# STM32.net
KiCad netlist of a schematic drawn in Altium Designer
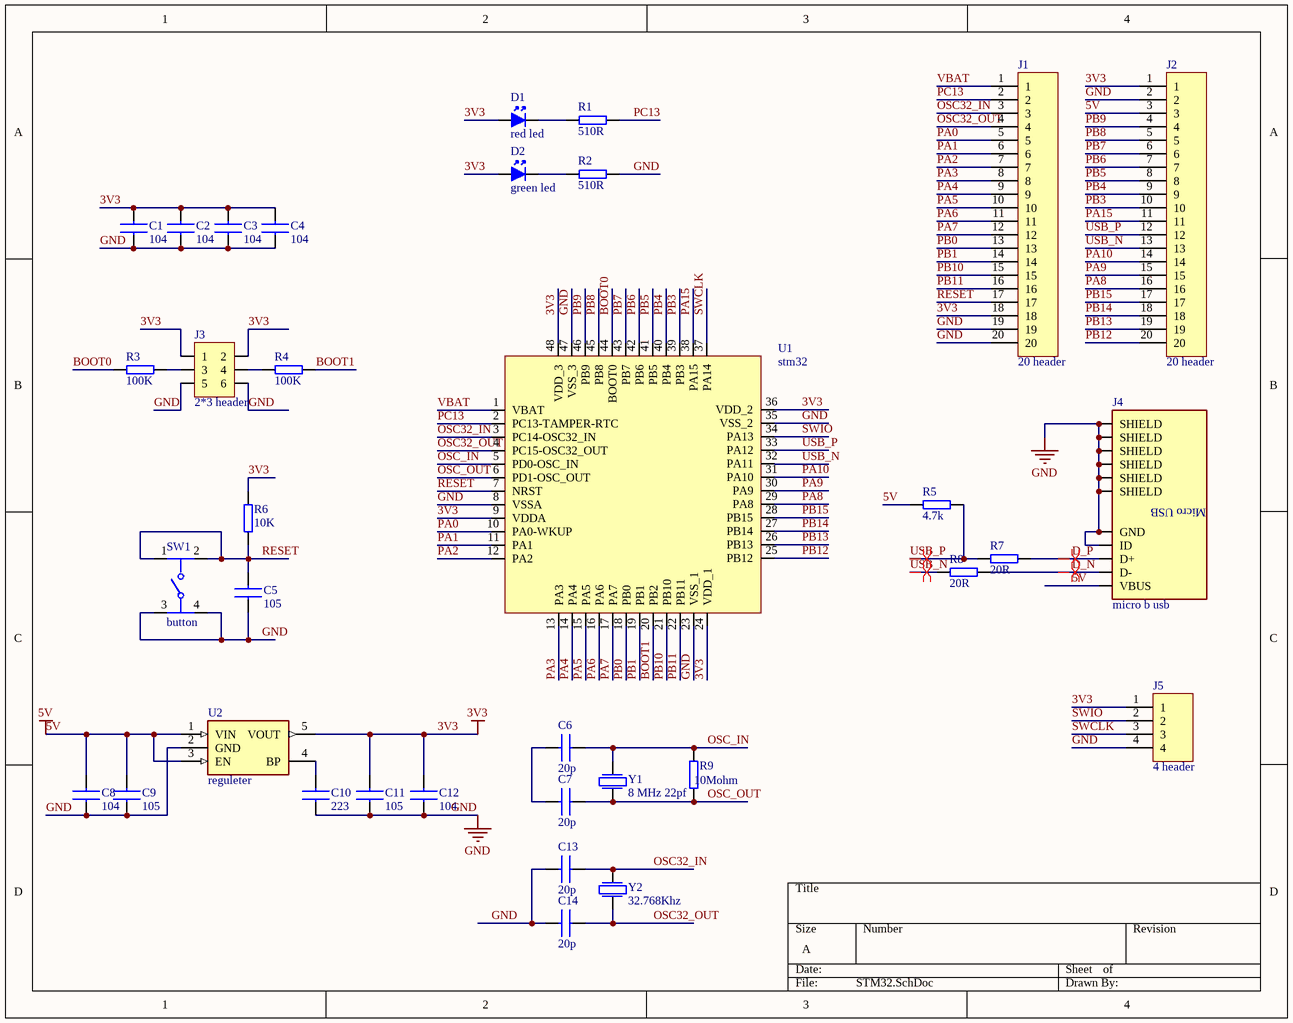
[diagram p0: STM32.SchDoc]

(export (version "E")
  (design (tool "Eeschema 10.0.6"))
  (components
    (comp (ref "C1")
      (value "104")
      (footprint "cap 0603")
      (description "0603")
      (libsource (lib "stm32") (part "104,0603"))
    )
    (comp (ref "C2")
      (value "104")
      (footprint "cap 0603")
      (description "0603")
      (libsource (lib "stm32") (part "104,0603"))
    )
    (comp (ref "C3")
      (value "104")
      (footprint "cap 0603")
      (description "0603")
      (libsource (lib "stm32") (part "104,0603"))
    )
    (comp (ref "C4")
      (value "104")
      (footprint "cap 0603")
      (description "0603")
      (libsource (lib "stm32") (part "104,0603"))
    )
    (comp (ref "C5")
      (value "105")
      (footprint "cap 0603")
      (description "0603")
      (libsource (lib "stm32") (part "105,0603"))
    )
    (comp (ref "C6")
      (value "20p")
      (footprint "cap 0603")
      (description "0603")
      (libsource (lib "stm32") (part "20p,0603"))
    )
    (comp (ref "C7")
      (value "20p")
      (footprint "cap 0603")
      (description "0603")
      (libsource (lib "stm32") (part "20p,0603"))
    )
    (comp (ref "C8")
      (value "104")
      (footprint "cap 0603")
      (description "0603")
      (libsource (lib "stm32") (part "104,0603"))
    )
    (comp (ref "C9")
      (value "105")
      (footprint "CAP 0805")
      (description "0805")
      (libsource (lib "stm32") (part "105,0805"))
    )
    (comp (ref "C10")
      (value "223")
      (footprint "cap 0603")
      (description "0603")
      (libsource (lib "stm32") (part "223,0603"))
    )
    (comp (ref "C11")
      (value "105")
      (footprint "CAP 0805")
      (description "0805")
      (libsource (lib "stm32") (part "105,0805"))
    )
    (comp (ref "C12")
      (value "104")
      (footprint "cap 0603")
      (description "0603")
      (libsource (lib "stm32") (part "104,0603"))
    )
    (comp (ref "C13")
      (value "20p")
      (footprint "cap 0603")
      (description "0603")
      (libsource (lib "stm32") (part "20p,0603"))
    )
    (comp (ref "C14")
      (value "20p")
      (footprint "cap 0603")
      (description "0603")
      (libsource (lib "stm32") (part "20p,0603"))
    )
    (comp (ref "D1") (value "red led") (footprint "red led") (libsource (lib "stm32") (part "red led")))
    (comp (ref "D2") (value "green led") (footprint "led green") (libsource (lib "stm32") (part "green led")))
    (comp (ref "J1")
      (value "20 header")
      (footprint "20*1 header")
      (libsource (lib "stm32") (part "20 header"))
    )
    (comp (ref "J2")
      (value "20 header")
      (footprint "20*1 header")
      (libsource (lib "stm32") (part "20 header"))
    )
    (comp (ref "J3")
      (value "2*3 header")
      (footprint "2*3 header")
      (libsource (lib "stm32") (part "2*3 header"))
    )
    (comp (ref "J4")
      (value "micro b usb")
      (footprint "micro-b usb")
      (libsource (lib "stm32") (part "micro-b usb"))
    )
    (comp (ref "J5") (value "4 header") (footprint "4 header") (libsource (lib "stm32") (part "4 header")))
    (comp (ref "R1")
      (value "510R")
      (footprint "res 0603")
      (description "0603")
      (libsource (lib "stm32") (part "510R"))
    )
    (comp (ref "R2")
      (value "510R")
      (footprint "res 0603")
      (description "0603")
      (libsource (lib "stm32") (part "510R"))
    )
    (comp (ref "R3")
      (value "100K")
      (footprint "res 0603")
      (description "0603")
      (libsource (lib "stm32") (part "100K"))
    )
    (comp (ref "R4")
      (value "100K")
      (footprint "res 0603")
      (description "0603")
      (libsource (lib "stm32") (part "100K"))
    )
    (comp (ref "R5")
      (value "4.7k")
      (footprint "res 0603")
      (description "0603")
      (libsource (lib "stm32") (part "4.7k,0603"))
    )
    (comp (ref "R6")
      (value "10K")
      (footprint "res 0603")
      (description "0603")
      (libsource (lib "stm32") (part "10K"))
    )
    (comp (ref "R7")
      (value "20R")
      (footprint "res 0603")
      (description "0603")
      (libsource (lib "stm32") (part "20R"))
    )
    (comp (ref "R8")
      (value "20R")
      (footprint "res 0603")
      (description "0603")
      (libsource (lib "stm32") (part "20R"))
    )
    (comp (ref "R9")
      (value "10Mohm")
      (footprint "res 0603")
      (description "10 MOhms ±5% 0.125W, 1/8W Chip Resistor 0805 (2012 Metric) High Voltage, Non-Magnetic Thick Film")
      (fields (field (name "JLCPCB PART #") "C4095037"))
      (libsource (lib "stm32") (part "10Mohm"))
    )
    (comp (ref "SW1")
      (value "button")
      (footprint "button")
      (description "Keypad Switch, 0.05A, 12VDC, 2.55N, , Surface Mount-straight")
      (fields
        (field (name "MANUFACTURER") "ITT C&K")
        (field (name "MANUFACTURER PART NUMBER") "PTS645SK43SMTR92LFS")
      )
      (libsource (lib "stm32") (part "push button"))
    )
    (comp (ref "U1") (value "stm32") (footprint "stm32") (libsource (lib "stm32") (part "stm32")))
    (comp (ref "U2")
      (value "reguleter")
      (footprint "reguleter")
      (description "Linear Voltage Regulator IC Positive Fixed 1 Output 300mA TSOT-23-5")
      (fields (field (name "MP") "RT9193-33GB") (field (name "MF") "Richtek USA"))
      (libsource (lib "stm32") (part "reguleter"))
    )
    (comp (ref "Y1")
      (value "8 MHz 22pf")
      (footprint "8MHz cristal")
      (description "8 MHz ±30ppm Crystal 22pF 80 Ohms HC-49/US")
      (fields (field (name "JLCPCB PART #") "C6109242"))
      (libsource (lib "stm32") (part "8 MHz 22pf"))
    )
    (comp (ref "Y2") (value "32.768Khz") (footprint "32.768KHZ") (libsource (lib "stm32") (part "32.768Khz")))
  )
  (nets
    (net (code "1") (name "/BOOT0") (class "Default")
      (node (ref "R3") (pin "1") (pinfunction "1_1") (pintype "passive"))
      (node (ref "U1") (pin "44") (pinfunction "BOOT0_44") (pintype "passive"))
    )
    (net (code "2") (name "/BOOT1") (class "Default")
      (node (ref "R4") (pin "2") (pinfunction "2_2") (pintype "passive"))
      (node (ref "U1") (pin "20") (pinfunction "PB2_20") (pintype "passive"))
    )
    (net (code "3") (name "/D_N") (class "Default")
      (node (ref "J4") (pin "2") (pinfunction "D-_2") (pintype "bidirectional"))
      (node (ref "R8") (pin "2") (pinfunction "2_2") (pintype "passive"))
    )
    (net (code "4") (name "/D_P") (class "Default")
      (node (ref "J4") (pin "3") (pinfunction "D+_3") (pintype "bidirectional"))
      (node (ref "R7") (pin "2") (pinfunction "2_2") (pintype "passive"))
    )
    (net (code "5") (name "/OSC32_IN") (class "Default")
      (node (ref "C13") (pin "2") (pinfunction "2_2") (pintype "passive"))
      (node (ref "J1") (pin "3") (pinfunction "3_3") (pintype "passive"))
      (node (ref "U1") (pin "3") (pinfunction "PC14-OSC32_IN_3") (pintype "passive"))
      (node (ref "Y2") (pin "2") (pinfunction "2_2") (pintype "passive"))
    )
    (net (code "6") (name "/OSC32_OUT") (class "Default")
      (node (ref "C14") (pin "2") (pinfunction "2_2") (pintype "passive"))
      (node (ref "J1") (pin "4") (pinfunction "4_4") (pintype "passive"))
      (node (ref "U1") (pin "4") (pinfunction "PC15-OSC32_OUT_4") (pintype "passive"))
      (node (ref "Y2") (pin "1") (pinfunction "1_1") (pintype "passive"))
    )
    (net (code "7") (name "/OSC_IN") (class "Default")
      (node (ref "C6") (pin "2") (pinfunction "2_2") (pintype "passive"))
      (node (ref "R9") (pin "2") (pinfunction "2_2") (pintype "passive"))
      (node (ref "U1") (pin "5") (pinfunction "PD0-OSC_IN_5") (pintype "passive"))
      (node (ref "Y1") (pin "2") (pinfunction "2_2") (pintype "passive"))
    )
    (net (code "8") (name "/OSC_OUT") (class "Default")
      (node (ref "C7") (pin "2") (pinfunction "2_2") (pintype "passive"))
      (node (ref "R9") (pin "1") (pinfunction "1_1") (pintype "passive"))
      (node (ref "U1") (pin "6") (pinfunction "PD1-OSC_OUT_6") (pintype "passive"))
      (node (ref "Y1") (pin "1") (pinfunction "1_1") (pintype "passive"))
    )
    (net (code "9") (name "/PA0") (class "Default")
      (node (ref "J1") (pin "5") (pinfunction "5_5") (pintype "passive"))
      (node (ref "U1") (pin "10") (pinfunction "PA0-WKUP_10") (pintype "passive"))
    )
    (net (code "10") (name "/PA1") (class "Default")
      (node (ref "J1") (pin "6") (pinfunction "6_6") (pintype "passive"))
      (node (ref "U1") (pin "11") (pinfunction "PA1_11") (pintype "passive"))
    )
    (net (code "11") (name "/PA2") (class "Default")
      (node (ref "J1") (pin "7") (pinfunction "7_7") (pintype "passive"))
      (node (ref "U1") (pin "12") (pinfunction "PA2_12") (pintype "passive"))
    )
    (net (code "12") (name "/PA3") (class "Default")
      (node (ref "J1") (pin "8") (pinfunction "8_8") (pintype "passive"))
      (node (ref "U1") (pin "13") (pinfunction "PA3_13") (pintype "passive"))
    )
    (net (code "13") (name "/PA4") (class "Default")
      (node (ref "J1") (pin "9") (pinfunction "9_9") (pintype "passive"))
      (node (ref "U1") (pin "14") (pinfunction "PA4_14") (pintype "passive"))
    )
    (net (code "14") (name "/PA5") (class "Default")
      (node (ref "J1") (pin "10") (pinfunction "10_10") (pintype "passive"))
      (node (ref "U1") (pin "15") (pinfunction "PA5_15") (pintype "passive"))
    )
    (net (code "15") (name "/PA6") (class "Default")
      (node (ref "J1") (pin "11") (pinfunction "11_11") (pintype "passive"))
      (node (ref "U1") (pin "16") (pinfunction "PA6_16") (pintype "passive"))
    )
    (net (code "16") (name "/PA7") (class "Default")
      (node (ref "J1") (pin "12") (pinfunction "12_12") (pintype "passive"))
      (node (ref "U1") (pin "17") (pinfunction "PA7_17") (pintype "passive"))
    )
    (net (code "17") (name "/PA8") (class "Default")
      (node (ref "J2") (pin "16") (pinfunction "16_16") (pintype "passive"))
      (node (ref "U1") (pin "29") (pinfunction "PA8_29") (pintype "passive"))
    )
    (net (code "18") (name "/PA9") (class "Default")
      (node (ref "J2") (pin "15") (pinfunction "15_15") (pintype "passive"))
      (node (ref "U1") (pin "30") (pinfunction "PA9_30") (pintype "passive"))
    )
    (net (code "19") (name "/PA10") (class "Default")
      (node (ref "J2") (pin "14") (pinfunction "14_14") (pintype "passive"))
      (node (ref "U1") (pin "31") (pinfunction "PA10_31") (pintype "passive"))
    )
    (net (code "20") (name "/PA15") (class "Default")
      (node (ref "J2") (pin "11") (pinfunction "11_11") (pintype "passive"))
      (node (ref "U1") (pin "38") (pinfunction "PA15_38") (pintype "passive"))
    )
    (net (code "21") (name "/PB0") (class "Default")
      (node (ref "J1") (pin "13") (pinfunction "13_13") (pintype "passive"))
      (node (ref "U1") (pin "18") (pinfunction "PB0_18") (pintype "passive"))
    )
    (net (code "22") (name "/PB1") (class "Default")
      (node (ref "J1") (pin "14") (pinfunction "14_14") (pintype "passive"))
      (node (ref "U1") (pin "19") (pinfunction "PB1_19") (pintype "passive"))
    )
    (net (code "23") (name "/PB3") (class "Default")
      (node (ref "J2") (pin "10") (pinfunction "10_10") (pintype "passive"))
      (node (ref "U1") (pin "39") (pinfunction "PB3_39") (pintype "passive"))
    )
    (net (code "24") (name "/PB4") (class "Default")
      (node (ref "J2") (pin "9") (pinfunction "9_9") (pintype "passive"))
      (node (ref "U1") (pin "40") (pinfunction "PB4_40") (pintype "passive"))
    )
    (net (code "25") (name "/PB5") (class "Default")
      (node (ref "J2") (pin "8") (pinfunction "8_8") (pintype "passive"))
      (node (ref "U1") (pin "41") (pinfunction "PB5_41") (pintype "passive"))
    )
    (net (code "26") (name "/PB6") (class "Default")
      (node (ref "J2") (pin "7") (pinfunction "7_7") (pintype "passive"))
      (node (ref "U1") (pin "42") (pinfunction "PB6_42") (pintype "passive"))
    )
    (net (code "27") (name "/PB7") (class "Default")
      (node (ref "J2") (pin "6") (pinfunction "6_6") (pintype "passive"))
      (node (ref "U1") (pin "43") (pinfunction "PB7_43") (pintype "passive"))
    )
    (net (code "28") (name "/PB8") (class "Default")
      (node (ref "J2") (pin "5") (pinfunction "5_5") (pintype "passive"))
      (node (ref "U1") (pin "45") (pinfunction "PB8_45") (pintype "passive"))
    )
    (net (code "29") (name "/PB9") (class "Default")
      (node (ref "J2") (pin "4") (pinfunction "4_4") (pintype "passive"))
      (node (ref "U1") (pin "46") (pinfunction "PB9_46") (pintype "passive"))
    )
    (net (code "30") (name "/PB10") (class "Default")
      (node (ref "J1") (pin "15") (pinfunction "15_15") (pintype "passive"))
      (node (ref "U1") (pin "21") (pinfunction "PB10_21") (pintype "passive"))
    )
    (net (code "31") (name "/PB11") (class "Default")
      (node (ref "J1") (pin "16") (pinfunction "16_16") (pintype "passive"))
      (node (ref "U1") (pin "22") (pinfunction "PB11_22") (pintype "passive"))
    )
    (net (code "32") (name "/PB12") (class "Default")
      (node (ref "J2") (pin "20") (pinfunction "20_20") (pintype "passive"))
      (node (ref "U1") (pin "25") (pinfunction "PB12_25") (pintype "passive"))
    )
    (net (code "33") (name "/PB13") (class "Default")
      (node (ref "J2") (pin "19") (pinfunction "19_19") (pintype "passive"))
      (node (ref "U1") (pin "26") (pinfunction "PB13_26") (pintype "passive"))
    )
    (net (code "34") (name "/PB14") (class "Default")
      (node (ref "J2") (pin "18") (pinfunction "18_18") (pintype "passive"))
      (node (ref "U1") (pin "27") (pinfunction "PB14_27") (pintype "passive"))
    )
    (net (code "35") (name "/PB15") (class "Default")
      (node (ref "J2") (pin "17") (pinfunction "17_17") (pintype "passive"))
      (node (ref "U1") (pin "28") (pinfunction "PB15_28") (pintype "passive"))
    )
    (net (code "36") (name "/PC13") (class "Default")
      (node (ref "J1") (pin "2") (pinfunction "2_2") (pintype "passive"))
      (node (ref "R1") (pin "2") (pinfunction "2_2") (pintype "passive"))
      (node (ref "U1") (pin "2") (pinfunction "PC13-TAMPER-RTC_2") (pintype "passive"))
    )
    (net (code "37") (name "/RESET") (class "Default")
      (node (ref "C5") (pin "2") (pinfunction "2_2") (pintype "passive"))
      (node (ref "J1") (pin "17") (pinfunction "17_17") (pintype "passive"))
      (node (ref "R6") (pin "1") (pinfunction "1_1") (pintype "passive"))
      (node (ref "SW1") (pin "1") (pinfunction "1_1") (pintype "passive"))
      (node (ref "SW1") (pin "2") (pinfunction "2_2") (pintype "passive"))
      (node (ref "U1") (pin "7") (pinfunction "NRST_7") (pintype "passive"))
    )
    (net (code "38") (name "/SWCLK") (class "Default")
      (node (ref "J5") (pin "3") (pinfunction "3_3") (pintype "passive"))
      (node (ref "U1") (pin "37") (pinfunction "PA14_37") (pintype "passive"))
    )
    (net (code "39") (name "/SWIO") (class "Default")
      (node (ref "J5") (pin "2") (pinfunction "2_2") (pintype "passive"))
      (node (ref "U1") (pin "34") (pinfunction "PA13_34") (pintype "passive"))
    )
    (net (code "40") (name "/USB_N") (class "Default")
      (node (ref "J2") (pin "13") (pinfunction "13_13") (pintype "passive"))
      (node (ref "R8") (pin "1") (pinfunction "1_1") (pintype "passive"))
      (node (ref "U1") (pin "32") (pinfunction "PA11_32") (pintype "passive"))
    )
    (net (code "41") (name "/USB_P") (class "Default")
      (node (ref "J2") (pin "12") (pinfunction "12_12") (pintype "passive"))
      (node (ref "R5") (pin "2") (pinfunction "2_2") (pintype "passive"))
      (node (ref "R7") (pin "1") (pinfunction "1_1") (pintype "passive"))
      (node (ref "U1") (pin "33") (pinfunction "PA12_33") (pintype "passive"))
    )
    (net (code "42") (name "/VBAT") (class "Default")
      (node (ref "J1") (pin "1") (pinfunction "1_1") (pintype "passive"))
      (node (ref "U1") (pin "1") (pinfunction "VBAT_1") (pintype "passive"))
    )
    (net (code "43") (name "3V3") (class "Default")
      (node (ref "C1") (pin "2") (pinfunction "2_2") (pintype "passive"))
      (node (ref "C11") (pin "2") (pinfunction "2_2") (pintype "passive"))
      (node (ref "C12") (pin "2") (pinfunction "2_2") (pintype "passive"))
      (node (ref "C2") (pin "2") (pinfunction "2_2") (pintype "passive"))
      (node (ref "C3") (pin "2") (pinfunction "2_2") (pintype "passive"))
      (node (ref "C4") (pin "2") (pinfunction "2_2") (pintype "passive"))
      (node (ref "D1") (pin "2") (pinfunction "2_2") (pintype "passive"))
      (node (ref "D2") (pin "2") (pinfunction "2_2") (pintype "passive"))
      (node (ref "J1") (pin "18") (pinfunction "18_18") (pintype "passive"))
      (node (ref "J2") (pin "1") (pinfunction "1_1") (pintype "passive"))
      (node (ref "J3") (pin "1") (pinfunction "1_1") (pintype "passive"))
      (node (ref "J3") (pin "2") (pinfunction "2_2") (pintype "passive"))
      (node (ref "J5") (pin "1") (pinfunction "1_1") (pintype "passive"))
      (node (ref "R6") (pin "2") (pinfunction "2_2") (pintype "passive"))
      (node (ref "U1") (pin "24") (pinfunction "VDD_1_24") (pintype "passive"))
      (node (ref "U1") (pin "36") (pinfunction "VDD_2_36") (pintype "passive"))
      (node (ref "U1") (pin "48") (pinfunction "VDD_3_48") (pintype "passive"))
      (node (ref "U1") (pin "9") (pinfunction "VDDA_9") (pintype "passive"))
      (node (ref "U2") (pin "5") (pinfunction "VOUT_5") (pintype "output"))
    )
    (net (code "44") (name "5V") (class "Default")
      (node (ref "C8") (pin "2") (pinfunction "2_2") (pintype "passive"))
      (node (ref "C9") (pin "2") (pinfunction "2_2") (pintype "passive"))
      (node (ref "J2") (pin "3") (pinfunction "3_3") (pintype "passive"))
      (node (ref "J4") (pin "1") (pinfunction "VBUS_1") (pintype "power_in"))
      (node (ref "R5") (pin "1") (pinfunction "1_1") (pintype "passive"))
      (node (ref "U2") (pin "1") (pinfunction "VIN_1") (pintype "input"))
      (node (ref "U2") (pin "3") (pinfunction "EN_3") (pintype "input"))
    )
    (net (code "45") (name "GND") (class "Default")
      (node (ref "C1") (pin "1") (pinfunction "1_1") (pintype "passive"))
      (node (ref "C10") (pin "1") (pinfunction "1_1") (pintype "passive"))
      (node (ref "C11") (pin "1") (pinfunction "1_1") (pintype "passive"))
      (node (ref "C12") (pin "1") (pinfunction "1_1") (pintype "passive"))
      (node (ref "C13") (pin "1") (pinfunction "1_1") (pintype "passive"))
      (node (ref "C14") (pin "1") (pinfunction "1_1") (pintype "passive"))
      (node (ref "C2") (pin "1") (pinfunction "1_1") (pintype "passive"))
      (node (ref "C3") (pin "1") (pinfunction "1_1") (pintype "passive"))
      (node (ref "C4") (pin "1") (pinfunction "1_1") (pintype "passive"))
      (node (ref "C5") (pin "1") (pinfunction "1_1") (pintype "passive"))
      (node (ref "C8") (pin "1") (pinfunction "1_1") (pintype "passive"))
      (node (ref "C9") (pin "1") (pinfunction "1_1") (pintype "passive"))
      (node (ref "J1") (pin "19") (pinfunction "19_19") (pintype "passive"))
      (node (ref "J1") (pin "20") (pinfunction "20_20") (pintype "passive"))
      (node (ref "J2") (pin "2") (pinfunction "2_2") (pintype "passive"))
      (node (ref "J3") (pin "5") (pinfunction "5_5") (pintype "passive"))
      (node (ref "J3") (pin "6") (pinfunction "6_6") (pintype "passive"))
      (node (ref "J4") (pin "4") (pinfunction "ID_4") (pintype "passive"))
      (node (ref "J4") (pin "5") (pinfunction "GND_5") (pintype "passive"))
      (node (ref "J4") (pin "SH1") (pinfunction "SHIELD_SH1") (pintype "passive"))
      (node (ref "J4") (pin "SH2") (pinfunction "SHIELD_SH2") (pintype "passive"))
      (node (ref "J4") (pin "SH3") (pinfunction "SHIELD_SH3") (pintype "passive"))
      (node (ref "J4") (pin "SH4") (pinfunction "SHIELD_SH4") (pintype "passive"))
      (node (ref "J4") (pin "SH5") (pinfunction "SHIELD_SH5") (pintype "passive"))
      (node (ref "J4") (pin "SH6") (pinfunction "SHIELD_SH6") (pintype "passive"))
      (node (ref "J5") (pin "4") (pinfunction "4_4") (pintype "passive"))
      (node (ref "R2") (pin "2") (pinfunction "2_2") (pintype "passive"))
      (node (ref "SW1") (pin "3") (pinfunction "3_3") (pintype "passive"))
      (node (ref "SW1") (pin "4") (pinfunction "4_4") (pintype "passive"))
      (node (ref "U1") (pin "23") (pinfunction "VSS_1_23") (pintype "passive"))
      (node (ref "U1") (pin "35") (pinfunction "VSS_2_35") (pintype "passive"))
      (node (ref "U1") (pin "47") (pinfunction "VSS_3_47") (pintype "passive"))
      (node (ref "U1") (pin "8") (pinfunction "VSSA_8") (pintype "passive"))
      (node (ref "U2") (pin "2") (pinfunction "GND_2") (pintype "passive"))
    )
    (net (code "46") (name "Net-(C6-Pad1)") (class "Default")
      (node (ref "C6") (pin "1") (pinfunction "1_1") (pintype "passive"))
      (node (ref "C7") (pin "1") (pinfunction "1_1") (pintype "passive"))
    )
    (net (code "47") (name "Net-(D1-Pad1)") (class "Default")
      (node (ref "D1") (pin "1") (pinfunction "1_1") (pintype "passive"))
      (node (ref "R1") (pin "1") (pinfunction "1_1") (pintype "passive"))
    )
    (net (code "48") (name "Net-(D2-Pad1)") (class "Default")
      (node (ref "D2") (pin "1") (pinfunction "1_1") (pintype "passive"))
      (node (ref "R2") (pin "1") (pinfunction "1_1") (pintype "passive"))
    )
    (net (code "49") (name "Net-(J3-Pad3)") (class "Default")
      (node (ref "J3") (pin "3") (pinfunction "3_3") (pintype "passive"))
      (node (ref "R3") (pin "2") (pinfunction "2_2") (pintype "passive"))
    )
    (net (code "50") (name "Net-(J3-Pad4)") (class "Default")
      (node (ref "J3") (pin "4") (pinfunction "4_4") (pintype "passive"))
      (node (ref "R4") (pin "1") (pinfunction "1_1") (pintype "passive"))
    )
    (net (code "51") (name "Net-(U2-BP)") (class "Default")
      (node (ref "C10") (pin "2") (pinfunction "2_2") (pintype "passive"))
      (node (ref "U2") (pin "4") (pinfunction "BP_4") (pintype "passive"))
    )
  )
)
